# DE-060718.net
KiCad netlist of a schematic drawn in Altium Designer
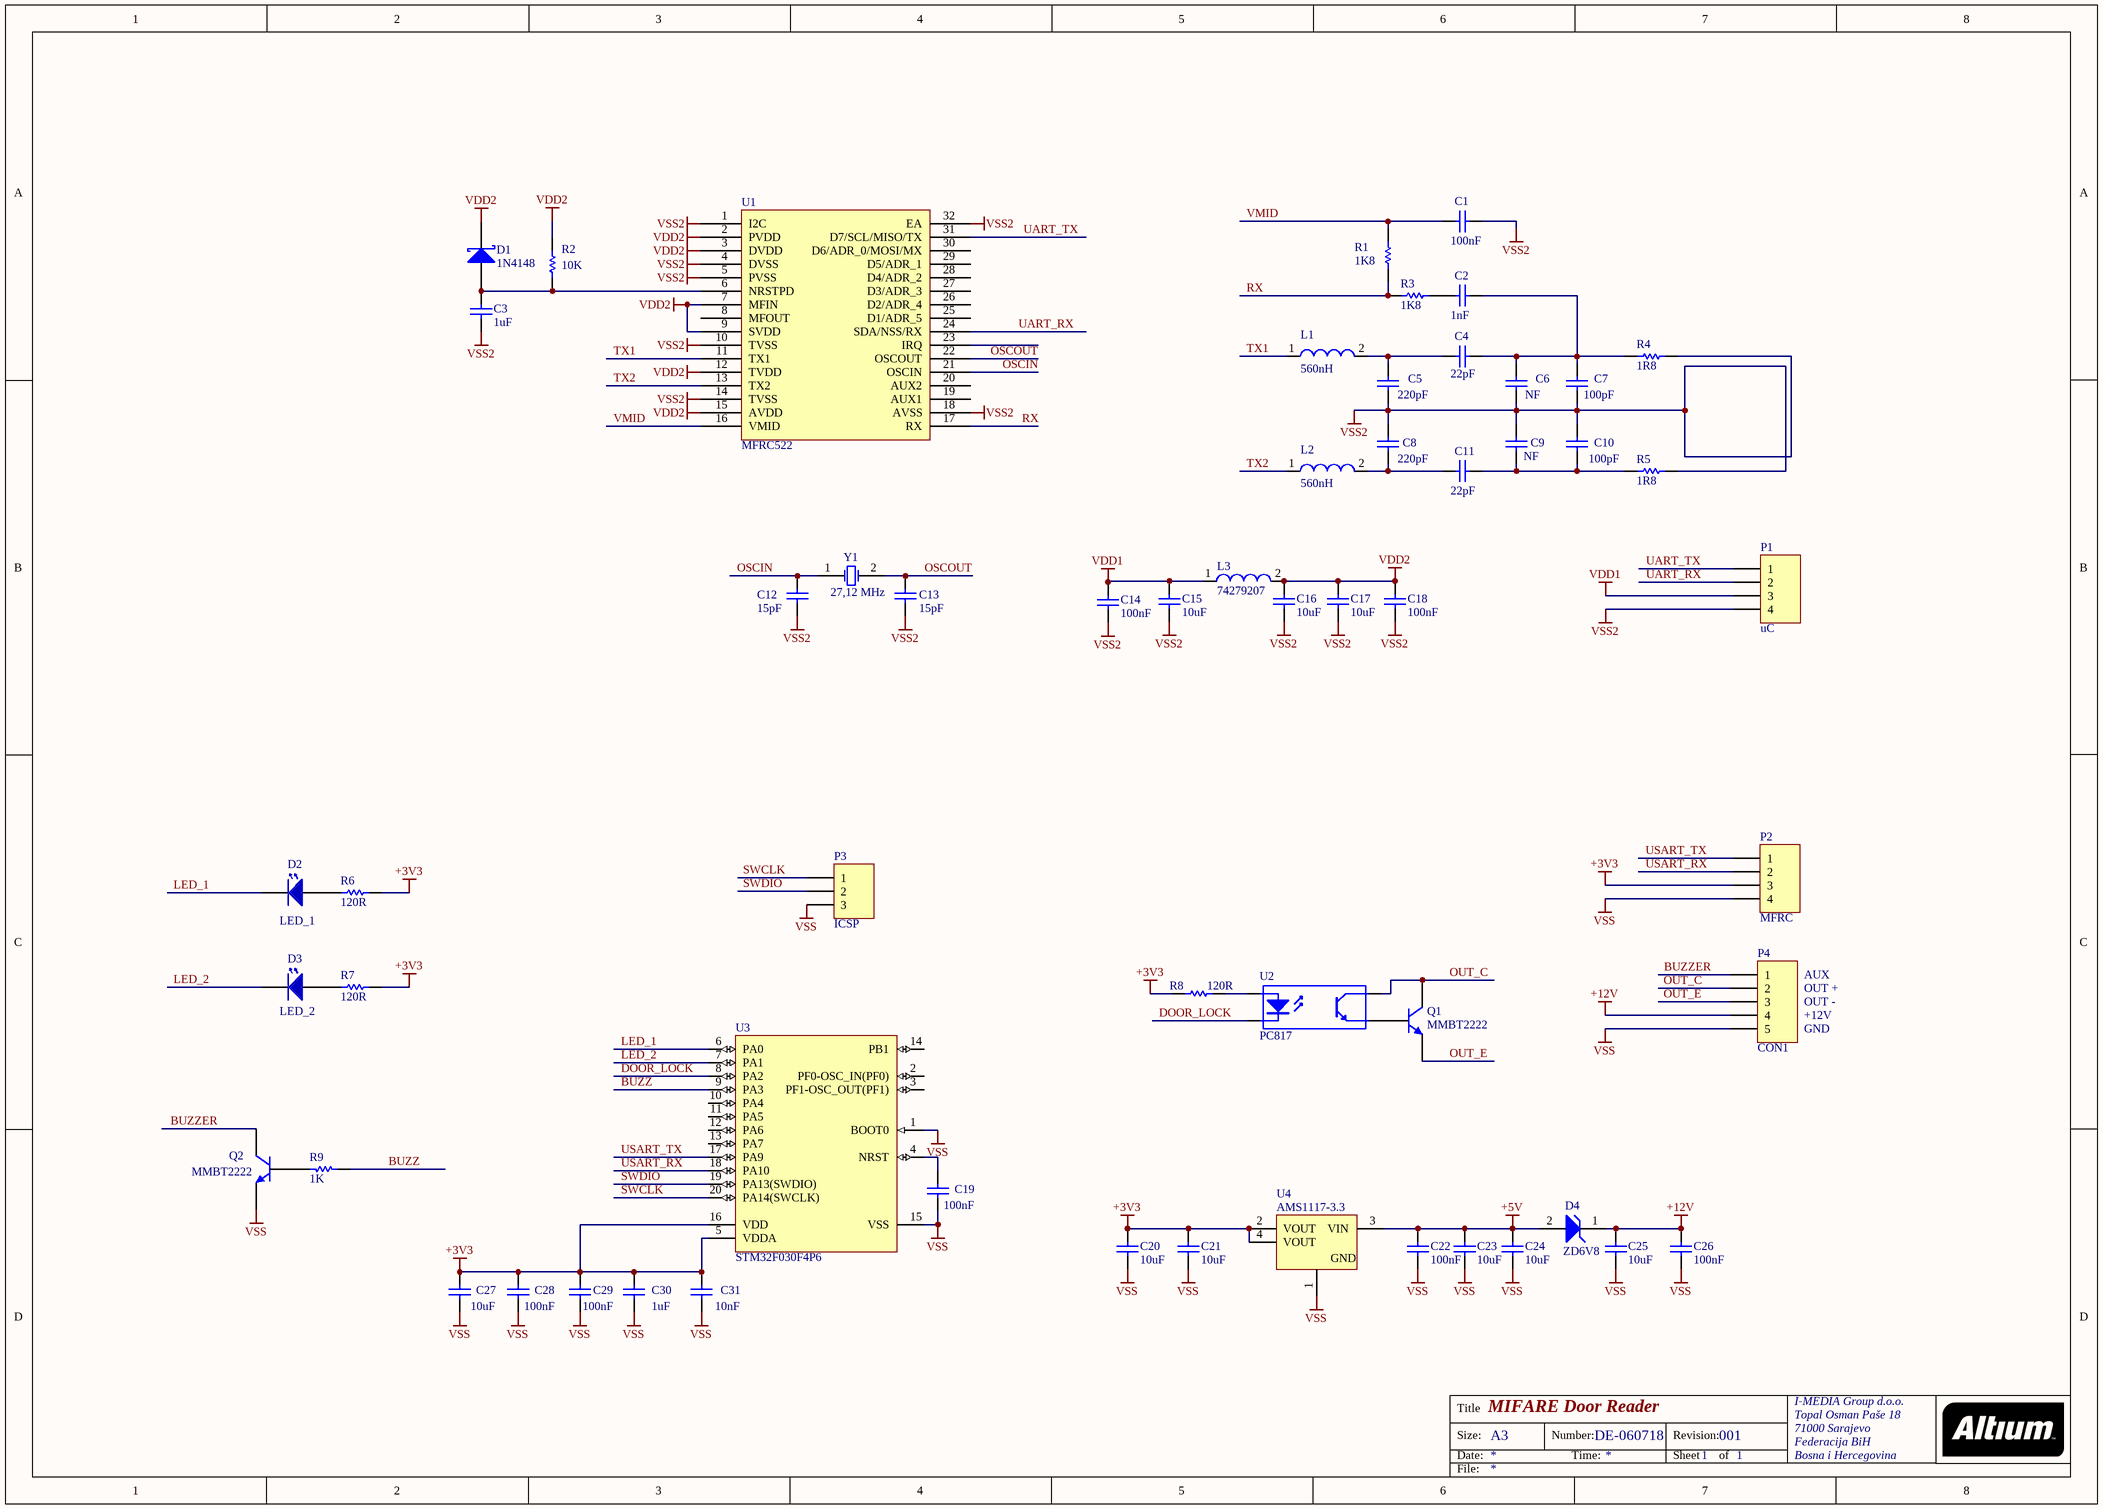
[diagram p0: DE-060718.SchDoc]

(export (version "E")
  (design (tool "Eeschema 10.0.6"))
  (components
    (comp (ref "C1")
      (value "100nF")
      (footprint "0603")
      (description "Ceramic Chip Capacitor - Standard")
      (fields (field (name "PUBLISHER") "Altium Limited"))
      (libsource (lib "KEMET Chip Capacitor") (part "C0603"))
    )
    (comp (ref "C2")
      (value "1nF")
      (footprint "0603")
      (description "Ceramic Chip Capacitor - Standard")
      (fields (field (name "PUBLISHER") "Altium Limited"))
      (libsource (lib "KEMET Chip Capacitor") (part "C0603"))
    )
    (comp (ref "C3")
      (value "1uF")
      (footprint "0603")
      (description "Ceramic Chip Capacitor - Standard")
      (fields (field (name "PUBLISHER") "Altium Limited"))
      (libsource (lib "sch_library") (part "C0603"))
    )
    (comp (ref "C4")
      (value "22pF")
      (footprint "0603")
      (description "Ceramic Chip Capacitor - Standard")
      (fields (field (name "PUBLISHER") "Altium Limited"))
      (libsource (lib "KEMET Chip Capacitor") (part "C0603"))
    )
    (comp (ref "C5")
      (value "220pF")
      (footprint "0603")
      (description "Ceramic Chip Capacitor - Standard")
      (fields (field (name "PUBLISHER") "Altium Limited"))
      (libsource (lib "KEMET Chip Capacitor") (part "C0603"))
    )
    (comp (ref "C6")
      (value "NF")
      (footprint "0603")
      (description "Ceramic Chip Capacitor - Standard")
      (fields (field (name "PUBLISHER") "Altium Limited"))
      (libsource (lib "KEMET Chip Capacitor") (part "C0603"))
    )
    (comp (ref "C7")
      (value "100pF")
      (footprint "0603")
      (description "Ceramic Chip Capacitor - Standard")
      (fields (field (name "PUBLISHER") "Altium Limited"))
      (libsource (lib "KEMET Chip Capacitor") (part "C0603"))
    )
    (comp (ref "C8")
      (value "220pF")
      (footprint "0603")
      (description "Ceramic Chip Capacitor - Standard")
      (fields (field (name "PUBLISHER") "Altium Limited"))
      (libsource (lib "KEMET Chip Capacitor") (part "C0603"))
    )
    (comp (ref "C9")
      (value "NF")
      (footprint "0603")
      (description "Ceramic Chip Capacitor - Standard")
      (fields (field (name "PUBLISHER") "Altium Limited"))
      (libsource (lib "KEMET Chip Capacitor") (part "C0603"))
    )
    (comp (ref "C10")
      (value "100pF")
      (footprint "0603")
      (description "Ceramic Chip Capacitor - Standard")
      (fields (field (name "PUBLISHER") "Altium Limited"))
      (libsource (lib "KEMET Chip Capacitor") (part "C0603"))
    )
    (comp (ref "C11")
      (value "22pF")
      (footprint "0603")
      (description "Ceramic Chip Capacitor - Standard")
      (fields (field (name "PUBLISHER") "Altium Limited"))
      (libsource (lib "KEMET Chip Capacitor") (part "C0603"))
    )
    (comp (ref "C12")
      (value "15pF")
      (footprint "0603")
      (description "Ceramic Chip Capacitor - Standard")
      (fields (field (name "PUBLISHER") "Altium Limited"))
      (libsource (lib "KEMET Chip Capacitor") (part "C0603"))
    )
    (comp (ref "C13")
      (value "15pF")
      (footprint "0603")
      (description "Ceramic Chip Capacitor - Standard")
      (fields (field (name "PUBLISHER") "Altium Limited"))
      (libsource (lib "KEMET Chip Capacitor") (part "C0603"))
    )
    (comp (ref "C14")
      (value "100nF")
      (footprint "0603")
      (description "Ceramic Chip Capacitor - Standard")
      (fields (field (name "PUBLISHER") "Altium Limited"))
      (libsource (lib "KEMET Chip Capacitor") (part "C0603"))
    )
    (comp (ref "C15")
      (value "10uF")
      (footprint "0805")
      (description "Ceramic Chip Capacitor - Standard")
      (fields (field (name "PUBLISHER") "Altium Limited"))
      (libsource (lib "KEMET Chip Capacitor") (part "C0805"))
    )
    (comp (ref "C16")
      (value "10uF")
      (footprint "0805")
      (description "Ceramic Chip Capacitor - Standard")
      (fields (field (name "PUBLISHER") "Altium Limited"))
      (libsource (lib "KEMET Chip Capacitor") (part "C0805"))
    )
    (comp (ref "C17")
      (value "10uF")
      (footprint "0805")
      (description "Ceramic Chip Capacitor - Standard")
      (fields (field (name "PUBLISHER") "Altium Limited"))
      (libsource (lib "KEMET Chip Capacitor") (part "C0805"))
    )
    (comp (ref "C18")
      (value "100nF")
      (footprint "0603")
      (description "Ceramic Chip Capacitor - Standard")
      (fields (field (name "PUBLISHER") "Altium Limited"))
      (libsource (lib "KEMET Chip Capacitor") (part "C0603"))
    )
    (comp (ref "C19")
      (value "100nF")
      (footprint "0603")
      (description "Ceramic Chip Capacitor - Standard")
      (fields (field (name "PUBLISHER") "Altium Limited"))
      (libsource (lib "KEMET Chip Capacitor") (part "C0603"))
    )
    (comp (ref "C20")
      (value "10uF")
      (footprint "0805")
      (description "Ceramic Chip Capacitor - Standard")
      (fields (field (name "PUBLISHER") "Altium Limited"))
      (libsource (lib "KEMET Chip Capacitor") (part "C0805"))
    )
    (comp (ref "C21")
      (value "10uF")
      (footprint "0805")
      (description "Ceramic Chip Capacitor - Standard")
      (fields (field (name "PUBLISHER") "Altium Limited"))
      (libsource (lib "KEMET Chip Capacitor") (part "C0805"))
    )
    (comp (ref "C22")
      (value "100nF")
      (footprint "0603")
      (description "Ceramic Chip Capacitor - Standard")
      (fields (field (name "PUBLISHER") "Altium Limited"))
      (libsource (lib "KEMET Chip Capacitor") (part "C0603"))
    )
    (comp (ref "C23")
      (value "10uF")
      (footprint "0805")
      (description "Ceramic Chip Capacitor - Standard")
      (fields (field (name "PUBLISHER") "Altium Limited"))
      (libsource (lib "KEMET Chip Capacitor") (part "C0805"))
    )
    (comp (ref "C24")
      (value "10uF")
      (footprint "0805")
      (description "Ceramic Chip Capacitor - Standard")
      (fields (field (name "PUBLISHER") "Altium Limited"))
      (libsource (lib "DE-071116") (part "C0805"))
    )
    (comp (ref "C25")
      (value "10uF")
      (footprint "0805")
      (description "Ceramic Chip Capacitor - Standard")
      (fields (field (name "PUBLISHER") "Altium Limited"))
      (libsource (lib "DE-071116") (part "C0805"))
    )
    (comp (ref "C26")
      (value "100nF")
      (footprint "0603")
      (description "Ceramic Chip Capacitor - Standard")
      (fields (field (name "PUBLISHER") "Altium Limited"))
      (libsource (lib "KEMET Chip Capacitor") (part "C0603"))
    )
    (comp (ref "C27")
      (value "10uF")
      (footprint "0805")
      (description "Ceramic Chip Capacitor - Standard")
      (fields (field (name "PUBLISHER") "Altium Limited"))
      (libsource (lib "KEMET Chip Capacitor") (part "C0805"))
    )
    (comp (ref "C28")
      (value "100nF")
      (footprint "0603")
      (description "Ceramic Chip Capacitor - Standard")
      (fields (field (name "PUBLISHER") "Altium Limited"))
      (libsource (lib "KEMET Chip Capacitor") (part "C0603"))
    )
    (comp (ref "C29")
      (value "100nF")
      (footprint "0603")
      (description "Ceramic Chip Capacitor - Standard")
      (fields (field (name "PUBLISHER") "Altium Limited"))
      (libsource (lib "KEMET Chip Capacitor") (part "C0603"))
    )
    (comp (ref "C30")
      (value "1uF")
      (footprint "0603")
      (description "Ceramic Chip Capacitor - Standard")
      (fields (field (name "PUBLISHER") "Altium Limited"))
      (libsource (lib "KEMET Chip Capacitor") (part "C0603"))
    )
    (comp (ref "C31")
      (value "10nF")
      (footprint "0603")
      (description "Ceramic Chip Capacitor - Standard")
      (fields (field (name "PUBLISHER") "Altium Limited"))
      (libsource (lib "KEMET Chip Capacitor") (part "C0603"))
    )
    (comp (ref "D1")
      (value "1N4148")
      (footprint "SOD323")
      (description "Schottky Barrier Diode")
      (fields (field (name "PUBLISHER") "Altium Limited"))
      (libsource (lib "sch_library") (part "1PS76SB10"))
    )
    (comp (ref "D2") (value "LED_1") (footprint "LED 3mm") (libsource (lib "sch_library") (part "LED 3mm")))
    (comp (ref "D3") (value "LED_2") (footprint "LED 3mm") (libsource (lib "sch_library") (part "LED 3mm")))
    (comp (ref "D4")
      (value "ZD6V8")
      (footprint "ONSC-SOD-123-2-425-04_V")
      (description "Zener Voltage Regulator, 500 mW, 2-Pin SOD-123, Pb-Free, Tape and Reel")
      (fields (field (name "MANUFACTURER") "On Semiconductor") (field (name "PARTNUMBER") "SZMMSZ6V8T1G"))
      (libsource (lib "ON Semi Zener Diodes") (part "SZMMSZ6V8T1G"))
    )
    (comp (ref "L1")
      (value "560nH")
      (footprint "SMD-0805")
      (description "SMD EMI Suppression Ferrite Bead WE-CBF, Z = 100 Ohm")
      (fields (field (name "PARTNUMBER") "74279207"))
      (libsource (lib "WE-CBF SMD EMI Suppression Ferrite Bead") (part "74279207"))
    )
    (comp (ref "L2")
      (value "560nH")
      (footprint "SMD-0805")
      (description "SMD EMI Suppression Ferrite Bead WE-CBF, Z = 100 Ohm")
      (fields (field (name "PARTNUMBER") "74279207"))
      (libsource (lib "WE-CBF SMD EMI Suppression Ferrite Bead") (part "74279207"))
    )
    (comp (ref "L3")
      (value "74279207")
      (footprint "SMD-0805")
      (description "SMD EMI Suppression Ferrite Bead WE-CBF, Z = 100 Ohm")
      (libsource (lib "WE-CBF SMD EMI Suppression Ferrite Bead") (part "74279207"))
    )
    (comp (ref "P1")
      (value "uC")
      (footprint "HDR1X4")
      (description "Header, 4-Pin")
      (fields (field (name "PUBLISHER") "Altium Limited"))
      (libsource (lib "DE-060718") (part "Header 4"))
    )
    (comp (ref "P2")
      (value "MFRC")
      (footprint "HDR1X4")
      (description "Header, 4-Pin")
      (fields (field (name "PUBLISHER") "Altium Limited"))
      (libsource (lib "DE-060718") (part "Header 4"))
    )
    (comp (ref "P3")
      (value "ICSP")
      (footprint "ICSP")
      (description "ICSP connection pads")
      (libsource (lib "DE-071116") (part "ICSP"))
    )
    (comp (ref "P4")
      (value "CON1")
      (footprint "HDR1X5")
      (description "Header, 5-Pin")
      (fields (field (name "PUBLISHER") "Altium Limited"))
      (libsource (lib "sch_library") (part "Header 5"))
    )
    (comp (ref "Q1")
      (value "MMBT2222")
      (footprint "SOT23_N")
      (description "NPN General-purpose Transistor")
      (fields (field (name "PUBLISHER") "Altium Limited"))
      (libsource (lib "DE-060718") (part "BC817"))
    )
    (comp (ref "Q2")
      (value "MMBT2222")
      (footprint "SOT23_N")
      (description "NPN General-purpose Transistor")
      (fields (field (name "PUBLISHER") "Altium Limited"))
      (libsource (lib "DE-060718") (part "BC817"))
    )
    (comp (ref "R1")
      (value "1K8")
      (footprint "ERA-0603")
      (fields (field (name "PUBLISHER") "Altium Limited"))
      (libsource (lib "Panasonic Resistor") (part "ERJ3RS"))
    )
    (comp (ref "R2")
      (value "10K")
      (footprint "ERA-0603")
      (fields (field (name "PUBLISHER") "Altium Limited"))
      (libsource (lib "Panasonic Resistor") (part "ERJ3RS"))
    )
    (comp (ref "R3")
      (value "1K8")
      (footprint "ERA-0603")
      (fields (field (name "PUBLISHER") "Altium Limited"))
      (libsource (lib "Panasonic Resistor") (part "ERJ3RS"))
    )
    (comp (ref "R4")
      (value "1R8")
      (footprint "ERA-0603")
      (fields (field (name "PUBLISHER") "Altium Limited"))
      (libsource (lib "Panasonic Resistor") (part "ERJ3RS"))
    )
    (comp (ref "R5")
      (value "1R8")
      (footprint "ERA-0603")
      (fields (field (name "PUBLISHER") "Altium Limited"))
      (libsource (lib "Panasonic Resistor") (part "ERJ3RS"))
    )
    (comp (ref "R6")
      (value "120R")
      (footprint "ERA-0603")
      (fields (field (name "PUBLISHER") "Altium Limited"))
      (libsource (lib "Panasonic Resistor") (part "ERJ3RS"))
    )
    (comp (ref "R7")
      (value "120R")
      (footprint "ERA-0603")
      (fields (field (name "PUBLISHER") "Altium Limited"))
      (libsource (lib "Panasonic Resistor") (part "ERJ3RS"))
    )
    (comp (ref "R8")
      (value "120R")
      (footprint "ERA-0603")
      (fields (field (name "PUBLISHER") "Altium Limited"))
      (libsource (lib "Panasonic Resistor") (part "ERJ3RS"))
    )
    (comp (ref "R9")
      (value "1K")
      (footprint "ERA-0603")
      (fields (field (name "PUBLISHER") "Altium Limited"))
      (libsource (lib "Panasonic Resistor") (part "ERJ3RS"))
    )
    (comp (ref "U1")
      (value "MFRC522")
      (footprint "QFN32")
      (description "MIFARE reader writer")
      (libsource (lib "DE-071116") (part "MFRC522"))
    )
    (comp (ref "U2")
      (value "PC817")
      (footprint "SOP4")
      (description "4-Pin Phototransistor Optocoupler")
      (fields (field (name "PUBLISHER") "Altium Limited"))
      (libsource (lib "DE-060718") (part "PC817 optocoupler"))
    )
    (comp (ref "U3")
      (value "STM32F030F4P6")
      (footprint "STM-TSSOP20_N")
      (libsource (lib "STMicroelectronics STM32 F0") (part "STM32F030F4P6"))
    )
    (comp (ref "U4")
      (value "AMS1117-3.3")
      (footprint "SOT-223_N")
      (description "1A, Low Drop Positive Voltage Regulator, 3.3V, 4-Pin SOT-223, Tape and Reel")
      (fields (field (name "PARTNUMBER") "LD1117AS33TR"))
      (libsource (lib "STMicroelectronics Power Management Linear Regulator") (part "LD1117AS33TR"))
    )
    (comp (ref "Y1")
      (value "27,12 MHz")
      (footprint "HC49/4H_SMX")
      (description "Surface Mount Quartz Crystal")
      (fields (field (name "PUBLISHER") "Altium Limited"))
      (libsource (lib "DE-071116") (part "HC49/4H_SMX"))
    )
  )
  (nets
    (net (code "1") (name "+3V3") (class "Default")
      (node (ref "C20") (pin "2") (pinfunction "2_2") (pintype "passive"))
      (node (ref "C21") (pin "2") (pinfunction "2_2") (pintype "passive"))
      (node (ref "C27") (pin "2") (pinfunction "2_2") (pintype "passive"))
      (node (ref "C28") (pin "2") (pinfunction "2_2") (pintype "passive"))
      (node (ref "C29") (pin "2") (pinfunction "2_2") (pintype "passive"))
      (node (ref "C30") (pin "2") (pinfunction "2_2") (pintype "passive"))
      (node (ref "C31") (pin "2") (pinfunction "2_2") (pintype "passive"))
      (node (ref "P2") (pin "3") (pinfunction "3_3") (pintype "passive"))
      (node (ref "R6") (pin "1") (pinfunction "1_1") (pintype "passive"))
      (node (ref "R7") (pin "1") (pinfunction "1_1") (pintype "passive"))
      (node (ref "R8") (pin "2") (pinfunction "2_2") (pintype "passive"))
      (node (ref "U3") (pin "16") (pinfunction "VDD_16") (pintype "power_in"))
      (node (ref "U3") (pin "5") (pinfunction "VDDA_5") (pintype "power_in"))
      (node (ref "U4") (pin "2") (pinfunction "VOUT_2") (pintype "power_in"))
      (node (ref "U4") (pin "4") (pinfunction "VOUT_4") (pintype "power_in"))
    )
    (net (code "2") (name "+5V") (class "Default")
      (node (ref "C22") (pin "2") (pinfunction "2_2") (pintype "passive"))
      (node (ref "C23") (pin "2") (pinfunction "2_2") (pintype "passive"))
      (node (ref "C24") (pin "2") (pinfunction "2_2") (pintype "passive"))
      (node (ref "D4") (pin "2") (pinfunction "A_2") (pintype "passive"))
      (node (ref "U4") (pin "3") (pinfunction "VIN_3") (pintype "power_in"))
    )
    (net (code "3") (name "+12V") (class "Default")
      (node (ref "C25") (pin "2") (pinfunction "2_2") (pintype "passive"))
      (node (ref "C26") (pin "2") (pinfunction "2_2") (pintype "passive"))
      (node (ref "D4") (pin "1") (pinfunction "K_1") (pintype "passive"))
      (node (ref "P4") (pin "4") (pinfunction "4_4") (pintype "passive"))
    )
    (net (code "4") (name "/BUZZ") (class "Default")
      (node (ref "R9") (pin "2") (pinfunction "2_2") (pintype "passive"))
      (node (ref "U3") (pin "9") (pinfunction "PA3_9") (pintype "bidirectional"))
    )
    (net (code "5") (name "/BUZZER") (class "Default")
      (node (ref "P4") (pin "1") (pinfunction "1_1") (pintype "passive"))
      (node (ref "Q2") (pin "3") (pinfunction "C_3") (pintype "passive"))
    )
    (net (code "6") (name "/DOOR_LOCK") (class "Default")
      (node (ref "U2") (pin "2") (pinfunction "K_2") (pintype "passive"))
      (node (ref "U3") (pin "8") (pinfunction "PA2_8") (pintype "bidirectional"))
    )
    (net (code "7") (name "/LED_1") (class "Default")
      (node (ref "D2") (pin "1") (pinfunction "1_1") (pintype "passive"))
      (node (ref "U3") (pin "6") (pinfunction "PA0_6") (pintype "bidirectional"))
    )
    (net (code "8") (name "/LED_2") (class "Default")
      (node (ref "D3") (pin "1") (pinfunction "1_1") (pintype "passive"))
      (node (ref "U3") (pin "7") (pinfunction "PA1_7") (pintype "bidirectional"))
    )
    (net (code "9") (name "/OSCIN") (class "Default")
      (node (ref "C12") (pin "2") (pinfunction "2_2") (pintype "passive"))
      (node (ref "U1") (pin "21") (pinfunction "OSCIN_21") (pintype "passive"))
      (node (ref "Y1") (pin "1") (pinfunction "OSC1_1") (pintype "passive"))
    )
    (net (code "10") (name "/OSCOUT") (class "Default")
      (node (ref "C13") (pin "2") (pinfunction "2_2") (pintype "passive"))
      (node (ref "U1") (pin "22") (pinfunction "OSCOUT_22") (pintype "passive"))
      (node (ref "Y1") (pin "2") (pinfunction "OSC2_2") (pintype "passive"))
    )
    (net (code "11") (name "/OUT_C") (class "Default")
      (node (ref "P4") (pin "2") (pinfunction "2_2") (pintype "passive"))
      (node (ref "Q1") (pin "3") (pinfunction "C_3") (pintype "passive"))
      (node (ref "U2") (pin "4") (pinfunction "C_4") (pintype "passive"))
    )
    (net (code "12") (name "/OUT_E") (class "Default")
      (node (ref "P4") (pin "3") (pinfunction "3_3") (pintype "passive"))
      (node (ref "Q1") (pin "2") (pinfunction "E_2") (pintype "passive"))
    )
    (net (code "13") (name "/RX") (class "Default")
      (node (ref "R1") (pin "2") (pinfunction "2_2") (pintype "passive"))
      (node (ref "R3") (pin "2") (pinfunction "2_2") (pintype "passive"))
      (node (ref "U1") (pin "17") (pinfunction "RX_17") (pintype "passive"))
    )
    (net (code "14") (name "/SWCLK") (class "Default")
      (node (ref "P3") (pin "1") (pinfunction "1_1") (pintype "passive"))
      (node (ref "U3") (pin "20") (pinfunction "PA14(SWCLK)_20") (pintype "bidirectional"))
    )
    (net (code "15") (name "/SWDIO") (class "Default")
      (node (ref "P3") (pin "2") (pinfunction "2_2") (pintype "passive"))
      (node (ref "U3") (pin "19") (pinfunction "PA13(SWDIO)_19") (pintype "bidirectional"))
    )
    (net (code "16") (name "/TX1") (class "Default")
      (node (ref "L1") (pin "1") (pinfunction "1_1") (pintype "passive"))
      (node (ref "U1") (pin "11") (pinfunction "TX1_11") (pintype "passive"))
    )
    (net (code "17") (name "/TX2") (class "Default")
      (node (ref "L2") (pin "1") (pinfunction "1_1") (pintype "passive"))
      (node (ref "U1") (pin "13") (pinfunction "TX2_13") (pintype "passive"))
    )
    (net (code "18") (name "/UART_RX") (class "Default")
      (node (ref "P1") (pin "2") (pinfunction "2_2") (pintype "passive"))
      (node (ref "U1") (pin "24") (pinfunction "SDA/NSS/RX_24") (pintype "passive"))
    )
    (net (code "19") (name "/UART_TX") (class "Default")
      (node (ref "P1") (pin "1") (pinfunction "1_1") (pintype "passive"))
      (node (ref "U1") (pin "31") (pinfunction "D7/SCL/MISO/TX_31") (pintype "passive"))
    )
    (net (code "20") (name "/USART_RX") (class "Default")
      (node (ref "P2") (pin "2") (pinfunction "2_2") (pintype "passive"))
      (node (ref "U3") (pin "18") (pinfunction "PA10_18") (pintype "bidirectional"))
    )
    (net (code "21") (name "/USART_TX") (class "Default")
      (node (ref "P2") (pin "1") (pinfunction "1_1") (pintype "passive"))
      (node (ref "U3") (pin "17") (pinfunction "PA9_17") (pintype "bidirectional"))
    )
    (net (code "22") (name "/VMID") (class "Default")
      (node (ref "C1") (pin "2") (pinfunction "2_2") (pintype "passive"))
      (node (ref "R1") (pin "1") (pinfunction "1_1") (pintype "passive"))
      (node (ref "U1") (pin "16") (pinfunction "VMID_16") (pintype "passive"))
    )
    (net (code "23") (name "Net-(C2-Pad1)") (class "Default")
      (node (ref "C2") (pin "1") (pinfunction "1_1") (pintype "passive"))
      (node (ref "C4") (pin "1") (pinfunction "1_1") (pintype "passive"))
      (node (ref "C6") (pin "2") (pinfunction "2_2") (pintype "passive"))
      (node (ref "C7") (pin "2") (pinfunction "2_2") (pintype "passive"))
      (node (ref "R4") (pin "2") (pinfunction "2_2") (pintype "passive"))
    )
    (net (code "24") (name "Net-(C2-Pad2)") (class "Default")
      (node (ref "C2") (pin "2") (pinfunction "2_2") (pintype "passive"))
      (node (ref "R3") (pin "1") (pinfunction "1_1") (pintype "passive"))
    )
    (net (code "25") (name "Net-(C4-Pad2)") (class "Default")
      (node (ref "C4") (pin "2") (pinfunction "2_2") (pintype "passive"))
      (node (ref "C5") (pin "2") (pinfunction "2_2") (pintype "passive"))
      (node (ref "L1") (pin "2") (pinfunction "2_2") (pintype "passive"))
    )
    (net (code "26") (name "Net-(C10-Pad1)") (class "Default")
      (node (ref "C10") (pin "1") (pinfunction "1_1") (pintype "passive"))
      (node (ref "C11") (pin "1") (pinfunction "1_1") (pintype "passive"))
      (node (ref "C9") (pin "1") (pinfunction "1_1") (pintype "passive"))
      (node (ref "R5") (pin "2") (pinfunction "2_2") (pintype "passive"))
    )
    (net (code "27") (name "Net-(C11-Pad2)") (class "Default")
      (node (ref "C11") (pin "2") (pinfunction "2_2") (pintype "passive"))
      (node (ref "C8") (pin "1") (pinfunction "1_1") (pintype "passive"))
      (node (ref "L2") (pin "2") (pinfunction "2_2") (pintype "passive"))
    )
    (net (code "28") (name "Net-(D1-A)") (class "Default")
      (node (ref "C3") (pin "2") (pinfunction "2_2") (pintype "passive"))
      (node (ref "D1") (pin "2") (pinfunction "A_2") (pintype "passive"))
      (node (ref "R2") (pin "1") (pinfunction "1_1") (pintype "passive"))
      (node (ref "U1") (pin "6") (pinfunction "NRSTPD_6") (pintype "passive"))
    )
    (net (code "29") (name "Net-(D2-Pad2)") (class "Default")
      (node (ref "D2") (pin "2") (pinfunction "2_2") (pintype "passive"))
      (node (ref "R6") (pin "2") (pinfunction "2_2") (pintype "passive"))
    )
    (net (code "30") (name "Net-(D3-Pad2)") (class "Default")
      (node (ref "D3") (pin "2") (pinfunction "2_2") (pintype "passive"))
      (node (ref "R7") (pin "2") (pinfunction "2_2") (pintype "passive"))
    )
    (net (code "31") (name "Net-(Q1-B)") (class "Default")
      (node (ref "Q1") (pin "1") (pinfunction "B_1") (pintype "passive"))
      (node (ref "U2") (pin "3") (pinfunction "E_3") (pintype "passive"))
    )
    (net (code "32") (name "Net-(Q2-B)") (class "Default")
      (node (ref "Q2") (pin "1") (pinfunction "B_1") (pintype "passive"))
      (node (ref "R9") (pin "1") (pinfunction "1_1") (pintype "passive"))
    )
    (net (code "33") (name "Net-(U2-A)") (class "Default")
      (node (ref "R8") (pin "1") (pinfunction "1_1") (pintype "passive"))
      (node (ref "U2") (pin "1") (pinfunction "A_1") (pintype "passive"))
    )
    (net (code "34") (name "Net-(U3-NRST)") (class "Default")
      (node (ref "C19") (pin "2") (pinfunction "2_2") (pintype "passive"))
      (node (ref "U3") (pin "4") (pinfunction "NRST_4") (pintype "bidirectional"))
    )
    (net (code "35") (name "VDD1") (class "Default")
      (node (ref "C14") (pin "2") (pinfunction "2_2") (pintype "passive"))
      (node (ref "C15") (pin "2") (pinfunction "2_2") (pintype "passive"))
      (node (ref "L3") (pin "1") (pinfunction "1_1") (pintype "passive"))
      (node (ref "P1") (pin "3") (pinfunction "3_3") (pintype "passive"))
    )
    (net (code "36") (name "VDD2") (class "Default")
      (node (ref "C16") (pin "2") (pinfunction "2_2") (pintype "passive"))
      (node (ref "C17") (pin "2") (pinfunction "2_2") (pintype "passive"))
      (node (ref "C18") (pin "2") (pinfunction "2_2") (pintype "passive"))
      (node (ref "D1") (pin "1") (pinfunction "K_1") (pintype "passive"))
      (node (ref "L3") (pin "2") (pinfunction "2_2") (pintype "passive"))
      (node (ref "R2") (pin "2") (pinfunction "2_2") (pintype "passive"))
      (node (ref "U1") (pin "12") (pinfunction "TVDD_12") (pintype "passive"))
      (node (ref "U1") (pin "15") (pinfunction "AVDD_15") (pintype "passive"))
      (node (ref "U1") (pin "2") (pinfunction "PVDD_2") (pintype "passive"))
      (node (ref "U1") (pin "3") (pinfunction "DVDD_3") (pintype "passive"))
      (node (ref "U1") (pin "7") (pinfunction "MFIN_7") (pintype "passive"))
      (node (ref "U1") (pin "9") (pinfunction "SVDD_9") (pintype "passive"))
    )
    (net (code "37") (name "VSS") (class "Default")
      (node (ref "C19") (pin "1") (pinfunction "1_1") (pintype "passive"))
      (node (ref "C20") (pin "1") (pinfunction "1_1") (pintype "passive"))
      (node (ref "C21") (pin "1") (pinfunction "1_1") (pintype "passive"))
      (node (ref "C22") (pin "1") (pinfunction "1_1") (pintype "passive"))
      (node (ref "C23") (pin "1") (pinfunction "1_1") (pintype "passive"))
      (node (ref "C24") (pin "1") (pinfunction "1_1") (pintype "passive"))
      (node (ref "C25") (pin "1") (pinfunction "1_1") (pintype "passive"))
      (node (ref "C26") (pin "1") (pinfunction "1_1") (pintype "passive"))
      (node (ref "C27") (pin "1") (pinfunction "1_1") (pintype "passive"))
      (node (ref "C28") (pin "1") (pinfunction "1_1") (pintype "passive"))
      (node (ref "C29") (pin "1") (pinfunction "1_1") (pintype "passive"))
      (node (ref "C30") (pin "1") (pinfunction "1_1") (pintype "passive"))
      (node (ref "C31") (pin "1") (pinfunction "1_1") (pintype "passive"))
      (node (ref "P2") (pin "4") (pinfunction "4_4") (pintype "passive"))
      (node (ref "P3") (pin "3") (pinfunction "3_3") (pintype "passive"))
      (node (ref "P4") (pin "5") (pinfunction "5_5") (pintype "passive"))
      (node (ref "Q2") (pin "2") (pinfunction "E_2") (pintype "passive"))
      (node (ref "U3") (pin "1") (pinfunction "BOOT0_1") (pintype "input"))
      (node (ref "U3") (pin "15") (pinfunction "VSS_15") (pintype "power_in"))
      (node (ref "U4") (pin "1") (pinfunction "GND_1") (pintype "power_in"))
    )
    (net (code "38") (name "VSS2") (class "Default")
      (node (ref "C1") (pin "1") (pinfunction "1_1") (pintype "passive"))
      (node (ref "C10") (pin "2") (pinfunction "2_2") (pintype "passive"))
      (node (ref "C12") (pin "1") (pinfunction "1_1") (pintype "passive"))
      (node (ref "C13") (pin "1") (pinfunction "1_1") (pintype "passive"))
      (node (ref "C14") (pin "1") (pinfunction "1_1") (pintype "passive"))
      (node (ref "C15") (pin "1") (pinfunction "1_1") (pintype "passive"))
      (node (ref "C16") (pin "1") (pinfunction "1_1") (pintype "passive"))
      (node (ref "C17") (pin "1") (pinfunction "1_1") (pintype "passive"))
      (node (ref "C18") (pin "1") (pinfunction "1_1") (pintype "passive"))
      (node (ref "C3") (pin "1") (pinfunction "1_1") (pintype "passive"))
      (node (ref "C5") (pin "1") (pinfunction "1_1") (pintype "passive"))
      (node (ref "C6") (pin "1") (pinfunction "1_1") (pintype "passive"))
      (node (ref "C7") (pin "1") (pinfunction "1_1") (pintype "passive"))
      (node (ref "C8") (pin "2") (pinfunction "2_2") (pintype "passive"))
      (node (ref "C9") (pin "2") (pinfunction "2_2") (pintype "passive"))
      (node (ref "P1") (pin "4") (pinfunction "4_4") (pintype "passive"))
      (node (ref "R4") (pin "1") (pinfunction "1_1") (pintype "passive"))
      (node (ref "R5") (pin "1") (pinfunction "1_1") (pintype "passive"))
      (node (ref "U1") (pin "1") (pinfunction "I2C_1") (pintype "passive"))
      (node (ref "U1") (pin "10") (pinfunction "TVSS_10") (pintype "passive"))
      (node (ref "U1") (pin "14") (pinfunction "TVSS_14") (pintype "passive"))
      (node (ref "U1") (pin "18") (pinfunction "AVSS_18") (pintype "passive"))
      (node (ref "U1") (pin "32") (pinfunction "EA_32") (pintype "passive"))
      (node (ref "U1") (pin "4") (pinfunction "DVSS_4") (pintype "passive"))
      (node (ref "U1") (pin "5") (pinfunction "PVSS_5") (pintype "passive"))
    )
    (net (code "39") (name "unconnected-(U1-AUX1-Pad19)") (class "Default")
      (node (ref "U1") (pin "19") (pinfunction "AUX1_19") (pintype "passive"))
    )
    (net (code "40") (name "unconnected-(U1-AUX2-Pad20)") (class "Default")
      (node (ref "U1") (pin "20") (pinfunction "AUX2_20") (pintype "passive"))
    )
    (net (code "41") (name "unconnected-(U1-D1{slash}ADR_5-Pad25)") (class "Default")
      (node (ref "U1") (pin "25") (pinfunction "D1/ADR_5_25") (pintype "passive"))
    )
    (net (code "42") (name "unconnected-(U1-D2{slash}ADR_4-Pad26)") (class "Default")
      (node (ref "U1") (pin "26") (pinfunction "D2/ADR_4_26") (pintype "passive"))
    )
    (net (code "43") (name "unconnected-(U1-D3{slash}ADR_3-Pad27)") (class "Default")
      (node (ref "U1") (pin "27") (pinfunction "D3/ADR_3_27") (pintype "passive"))
    )
    (net (code "44") (name "unconnected-(U1-D4{slash}ADR_2-Pad28)") (class "Default")
      (node (ref "U1") (pin "28") (pinfunction "D4/ADR_2_28") (pintype "passive"))
    )
    (net (code "45") (name "unconnected-(U1-D5{slash}ADR_1-Pad29)") (class "Default")
      (node (ref "U1") (pin "29") (pinfunction "D5/ADR_1_29") (pintype "passive"))
    )
    (net (code "46") (name "unconnected-(U1-D6{slash}ADR_0{slash}MOSI{slash}MX-Pad30)") (class "Default")
      (node (ref "U1") (pin "30") (pinfunction "D6/ADR_0/MOSI/MX_30") (pintype "passive"))
    )
    (net (code "47") (name "unconnected-(U1-IRQ-Pad23)") (class "Default")
      (node (ref "U1") (pin "23") (pinfunction "IRQ_23") (pintype "passive"))
    )
    (net (code "48") (name "unconnected-(U1-MFOUT-Pad8)") (class "Default")
      (node (ref "U1") (pin "8") (pinfunction "MFOUT_8") (pintype "passive"))
    )
    (net (code "49") (name "unconnected-(U1-Pad33)") (class "Default")
      (node (ref "U1") (pin "33") (pinfunction "33_33") (pintype "passive"))
    )
    (net (code "50") (name "unconnected-(U3-PA4-Pad10)") (class "Default")
      (node (ref "U3") (pin "10") (pinfunction "PA4_10") (pintype "bidirectional"))
    )
    (net (code "51") (name "unconnected-(U3-PA5-Pad11)") (class "Default")
      (node (ref "U3") (pin "11") (pinfunction "PA5_11") (pintype "bidirectional"))
    )
    (net (code "52") (name "unconnected-(U3-PA6-Pad12)") (class "Default")
      (node (ref "U3") (pin "12") (pinfunction "PA6_12") (pintype "bidirectional"))
    )
    (net (code "53") (name "unconnected-(U3-PA7-Pad13)") (class "Default")
      (node (ref "U3") (pin "13") (pinfunction "PA7_13") (pintype "bidirectional"))
    )
    (net (code "54") (name "unconnected-(U3-PB1-Pad14)") (class "Default")
      (node (ref "U3") (pin "14") (pinfunction "PB1_14") (pintype "bidirectional"))
    )
    (net (code "55") (name "unconnected-(U3-PF0-OSC_IN(PF0)-Pad2)") (class "Default")
      (node (ref "U3") (pin "2") (pinfunction "PF0-OSC_IN(PF0)_2") (pintype "bidirectional"))
    )
    (net (code "56") (name "unconnected-(U3-PF1-OSC_OUT(PF1)-Pad3)") (class "Default")
      (node (ref "U3") (pin "3") (pinfunction "PF1-OSC_OUT(PF1)_3") (pintype "bidirectional"))
    )
  )
)
